# ADC.net
KiCad netlist of a schematic drawn in Altium Designer
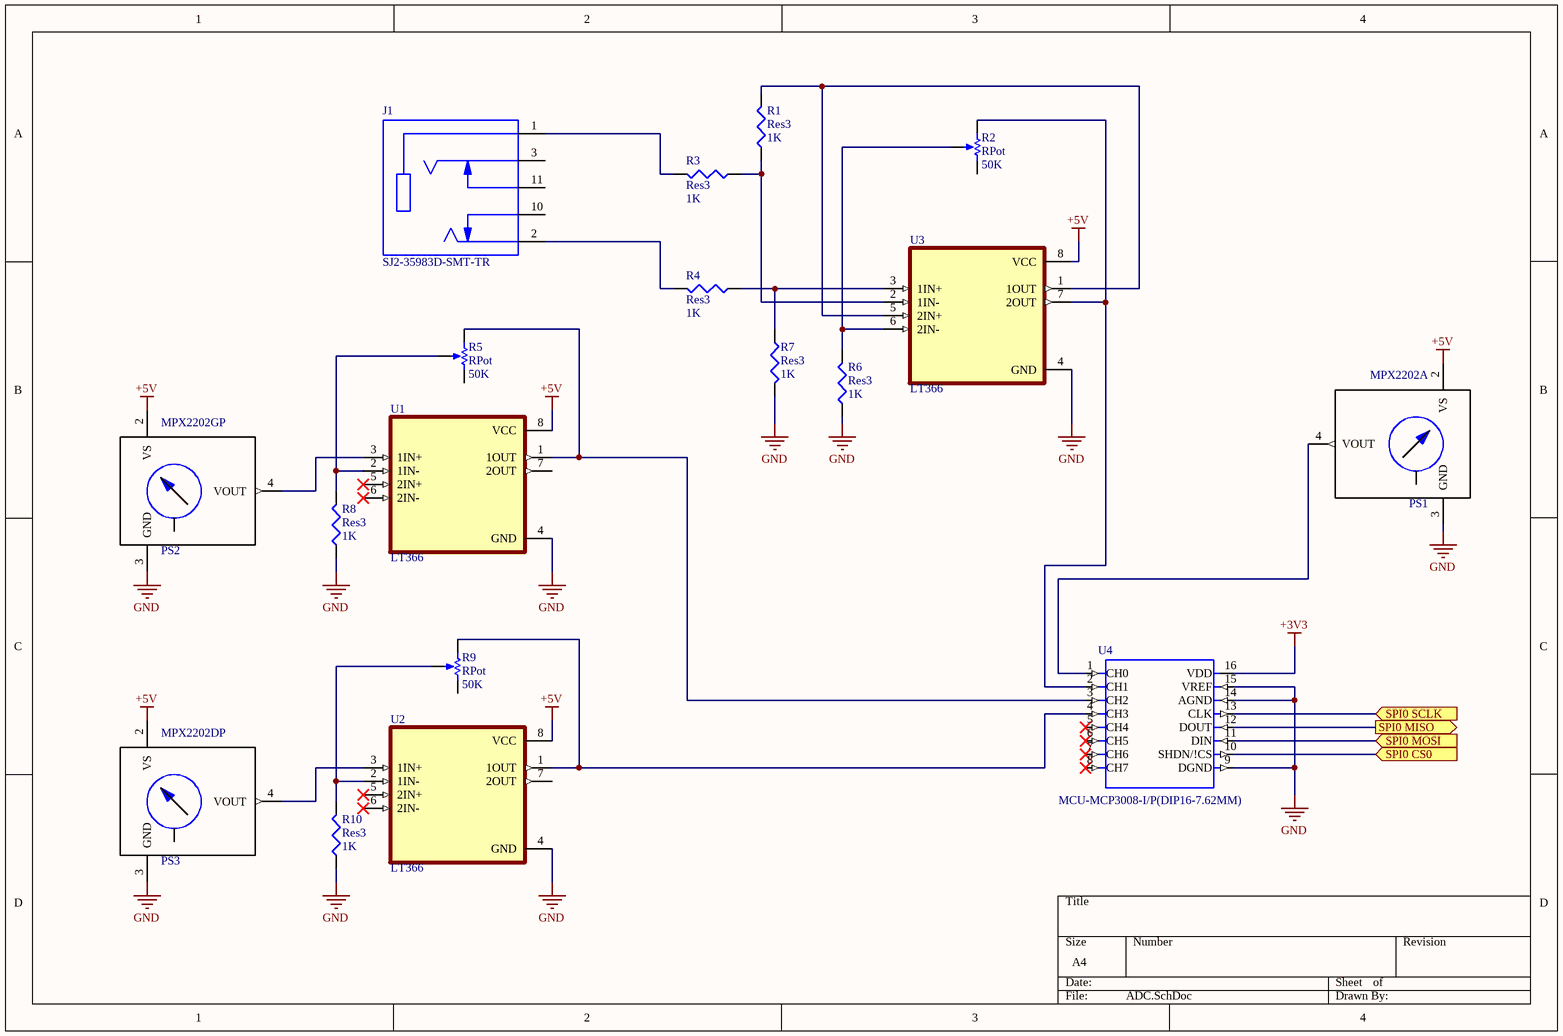
[diagram p0: ADC.SchDoc]

(export (version "E")
  (design (tool "Eeschema 10.0.6"))
  (components
    (comp (ref "J1")
      (value "SJ2-35983D-SMT-TR")
      (footprint "CUI_SJ2-35983D-SMT-TR")
      (description "3 conductor, 3.5 mm, SMT Audio Jack w/ 2 switch")
      (libsource (lib "SJ2-35983D-SMT-TR") (part "SJ2-35983D-SMT-TR"))
    )
    (comp (ref "PS1")
      (value "MPX2202A")
      (footprint "*867-V")
      (description "Low-Side Gate Driver IC Inverting, Non-Inverting 6-MLP (2x2)")
      (fields (field (name "MP") "MPX") (field (name "MF") "ON Semiconductor"))
      (libsource (lib "MPX_____") (part "MPX*****"))
    )
    (comp (ref "PS2")
      (value "MPX2202GP")
      (footprint "*867B-V")
      (description "Low-Side Gate Driver IC Inverting, Non-Inverting 6-MLP (2x2)")
      (fields (field (name "MP") "MPX") (field (name "MF") "ON Semiconductor"))
      (libsource (lib "MPX_____") (part "MPX*****"))
    )
    (comp (ref "PS3")
      (value "MPX2202DP")
      (footprint "*867C-V")
      (description "Low-Side Gate Driver IC Inverting, Non-Inverting 6-MLP (2x2)")
      (fields (field (name "MP") "MPX") (field (name "MF") "ON Semiconductor"))
      (libsource (lib "MPX_____") (part "MPX*****"))
    )
    (comp (ref "R1")
      (value "Res3")
      (footprint "J1-0603")
      (description "Resistor")
      (fields (field (name "ALTIUM_VALUE") "1K") (field (name "PUBLISHER") "Altium Limited"))
      (libsource (lib "Miscellaneous Devices") (part "Res3"))
    )
    (comp (ref "R2")
      (value "RPot")
      (footprint "VR5")
      (description "Potentiometer")
      (fields (field (name "ALTIUM_VALUE") "50K") (field (name "PUBLISHER") "Altium Limited"))
      (libsource (lib "Miscellaneous Devices") (part "RPot"))
    )
    (comp (ref "R3")
      (value "Res3")
      (footprint "J1-0603")
      (description "Resistor")
      (fields (field (name "ALTIUM_VALUE") "1K") (field (name "PUBLISHER") "Altium Limited"))
      (libsource (lib "Miscellaneous Devices") (part "Res3"))
    )
    (comp (ref "R4")
      (value "Res3")
      (footprint "J1-0603")
      (description "Resistor")
      (fields (field (name "ALTIUM_VALUE") "1K") (field (name "PUBLISHER") "Altium Limited"))
      (libsource (lib "Miscellaneous Devices") (part "Res3"))
    )
    (comp (ref "R5")
      (value "RPot")
      (footprint "VR5")
      (description "Potentiometer")
      (fields (field (name "ALTIUM_VALUE") "50K") (field (name "PUBLISHER") "Altium Limited"))
      (libsource (lib "Miscellaneous Devices") (part "RPot"))
    )
    (comp (ref "R6")
      (value "Res3")
      (footprint "J1-0603")
      (description "Resistor")
      (fields (field (name "ALTIUM_VALUE") "1K") (field (name "PUBLISHER") "Altium Limited"))
      (libsource (lib "Miscellaneous Devices") (part "Res3"))
    )
    (comp (ref "R7")
      (value "Res3")
      (footprint "J1-0603")
      (description "Resistor")
      (fields (field (name "ALTIUM_VALUE") "1K") (field (name "PUBLISHER") "Altium Limited"))
      (libsource (lib "Miscellaneous Devices") (part "Res3"))
    )
    (comp (ref "R8")
      (value "Res3")
      (footprint "J1-0603")
      (description "Resistor")
      (fields (field (name "ALTIUM_VALUE") "1K") (field (name "PUBLISHER") "Altium Limited"))
      (libsource (lib "Miscellaneous Devices") (part "Res3"))
    )
    (comp (ref "R9")
      (value "RPot")
      (footprint "VR5")
      (description "Potentiometer")
      (fields (field (name "ALTIUM_VALUE") "50K") (field (name "PUBLISHER") "Altium Limited"))
      (libsource (lib "Miscellaneous Devices") (part "RPot"))
    )
    (comp (ref "R10")
      (value "Res3")
      (footprint "J1-0603")
      (description "Resistor")
      (fields (field (name "ALTIUM_VALUE") "1K") (field (name "PUBLISHER") "Altium Limited"))
      (libsource (lib "Miscellaneous Devices") (part "Res3"))
    )
    (comp (ref "U1")
      (value "LT366")
      (footprint "DIP-8")
      (description "Dual Operational Amplifiers")
      (fields (field (name "MP") "LM358P") (field (name "MF") "Texas Instruments"))
      (libsource (lib "LM358P") (part "LM358P"))
    )
    (comp (ref "U2")
      (value "LT366")
      (footprint "DIP-8")
      (description "Dual Operational Amplifiers")
      (fields (field (name "MP") "LM358P") (field (name "MF") "Texas Instruments"))
      (libsource (lib "LM358P") (part "LM358P"))
    )
    (comp (ref "U3")
      (value "LT366")
      (footprint "DIP-8")
      (description "Dual Operational Amplifiers")
      (fields (field (name "MP") "LM358P") (field (name "MF") "Texas Instruments"))
      (libsource (lib "LM358P") (part "LM358P"))
    )
    (comp (ref "U4")
      (value "MCU-MCP3008-I/P(DIP16-7.62MM)")
      (footprint "DIP16-2.54-19.2X7.62MM")
      (description "10 Bit Analog to Digital Converter 4, 8 Input 1 SAR 16-PDIP")
      (fields (field (name "MF") "Microchip") (field (name "MP") "MCP3008-I/P"))
      (libsource (lib "MCU-MCP3008-I_P_DIP16-7.62MM_") (part "MCU-MCP3008-I/P(DIP16-7.62MM)"))
    )
  )
  (nets
    (net (code "1") (name "+3V3") (class "Default")
      (node (ref "U4") (pin "16") (pinfunction "VDD_16") (pintype "power_in"))
    )
    (net (code "2") (name "+5V") (class "Default")
      (node (ref "PS1") (pin "2") (pinfunction "VS_2") (pintype "power_in"))
      (node (ref "PS2") (pin "2") (pinfunction "VS_2") (pintype "power_in"))
      (node (ref "PS3") (pin "2") (pinfunction "VS_2") (pintype "power_in"))
      (node (ref "U1") (pin "8") (pinfunction "VCC_8") (pintype "power_in"))
      (node (ref "U2") (pin "8") (pinfunction "VCC_8") (pintype "power_in"))
      (node (ref "U3") (pin "8") (pinfunction "VCC_8") (pintype "power_in"))
    )
    (net (code "3") (name "/SPI0 CS0") (class "Default")
      (node (ref "U4") (pin "10") (pinfunction "SHDN/!CS_10") (pintype "output"))
    )
    (net (code "4") (name "/SPI0 MISO") (class "Default")
      (node (ref "U4") (pin "12") (pinfunction "DOUT_12") (pintype "input"))
    )
    (net (code "5") (name "/SPI0 MOSI") (class "Default")
      (node (ref "U4") (pin "11") (pinfunction "DIN_11") (pintype "input"))
    )
    (net (code "6") (name "/SPI0 SCLK") (class "Default")
      (node (ref "U4") (pin "13") (pinfunction "CLK_13") (pintype "output"))
    )
    (net (code "7") (name "GND") (class "Default")
      (node (ref "PS1") (pin "3") (pinfunction "GND_3") (pintype "power_in"))
      (node (ref "PS2") (pin "3") (pinfunction "GND_3") (pintype "power_in"))
      (node (ref "PS3") (pin "3") (pinfunction "GND_3") (pintype "power_in"))
      (node (ref "R10") (pin "1") (pinfunction "1_1") (pintype "passive"))
      (node (ref "R6") (pin "1") (pinfunction "1_1") (pintype "passive"))
      (node (ref "R7") (pin "2") (pinfunction "2_2") (pintype "passive"))
      (node (ref "R8") (pin "1") (pinfunction "1_1") (pintype "passive"))
      (node (ref "U1") (pin "4") (pinfunction "GND_4") (pintype "power_in"))
      (node (ref "U2") (pin "4") (pinfunction "GND_4") (pintype "power_in"))
      (node (ref "U3") (pin "4") (pinfunction "GND_4") (pintype "power_in"))
      (node (ref "U4") (pin "14") (pinfunction "AGND_14") (pintype "input"))
      (node (ref "U4") (pin "15") (pinfunction "VREF_15") (pintype "input"))
      (node (ref "U4") (pin "9") (pinfunction "DGND_9") (pintype "output"))
    )
    (net (code "8") (name "Net-(J1-SLEEVE)") (class "Default")
      (node (ref "J1") (pin "1") (pinfunction "SLEEVE_1") (pintype "passive"))
      (node (ref "R3") (pin "2") (pinfunction "2_2") (pintype "passive"))
    )
    (net (code "9") (name "Net-(J1-TIP)") (class "Default")
      (node (ref "J1") (pin "2") (pinfunction "TIP_2") (pintype "passive"))
      (node (ref "R4") (pin "2") (pinfunction "2_2") (pintype "passive"))
    )
    (net (code "10") (name "Net-(PS1-VOUT)") (class "Default")
      (node (ref "PS1") (pin "4") (pinfunction "VOUT_4") (pintype "output"))
      (node (ref "U4") (pin "1") (pinfunction "CH0_1") (pintype "input"))
    )
    (net (code "11") (name "Net-(PS2-VOUT)") (class "Default")
      (node (ref "PS2") (pin "4") (pinfunction "VOUT_4") (pintype "output"))
      (node (ref "U1") (pin "3") (pinfunction "1IN+_3") (pintype "input"))
    )
    (net (code "12") (name "Net-(PS3-VOUT)") (class "Default")
      (node (ref "PS3") (pin "4") (pinfunction "VOUT_4") (pintype "output"))
      (node (ref "U2") (pin "3") (pinfunction "1IN+_3") (pintype "input"))
    )
    (net (code "13") (name "Net-(R2-TAP)") (class "Default")
      (node (ref "R2") (pin "3") (pinfunction "TAP_3") (pintype "passive"))
      (node (ref "R6") (pin "2") (pinfunction "2_2") (pintype "passive"))
      (node (ref "U3") (pin "6") (pinfunction "2IN-_6") (pintype "input"))
    )
    (net (code "14") (name "Net-(R2-TOP)") (class "Default")
      (node (ref "R2") (pin "1") (pinfunction "TOP_1") (pintype "passive"))
      (node (ref "U3") (pin "7") (pinfunction "2OUT_7") (pintype "output"))
      (node (ref "U4") (pin "2") (pinfunction "CH1_2") (pintype "input"))
    )
    (net (code "15") (name "Net-(R5-TAP)") (class "Default")
      (node (ref "R5") (pin "3") (pinfunction "TAP_3") (pintype "passive"))
      (node (ref "R8") (pin "2") (pinfunction "2_2") (pintype "passive"))
      (node (ref "U1") (pin "2") (pinfunction "1IN-_2") (pintype "input"))
    )
    (net (code "16") (name "Net-(R5-TOP)") (class "Default")
      (node (ref "R5") (pin "1") (pinfunction "TOP_1") (pintype "passive"))
      (node (ref "U1") (pin "1") (pinfunction "1OUT_1") (pintype "output"))
      (node (ref "U4") (pin "3") (pinfunction "CH2_3") (pintype "input"))
    )
    (net (code "17") (name "Net-(R9-TAP)") (class "Default")
      (node (ref "R10") (pin "2") (pinfunction "2_2") (pintype "passive"))
      (node (ref "R9") (pin "3") (pinfunction "TAP_3") (pintype "passive"))
      (node (ref "U2") (pin "2") (pinfunction "1IN-_2") (pintype "input"))
    )
    (net (code "18") (name "Net-(R9-TOP)") (class "Default")
      (node (ref "R9") (pin "1") (pinfunction "TOP_1") (pintype "passive"))
      (node (ref "U2") (pin "1") (pinfunction "1OUT_1") (pintype "output"))
      (node (ref "U4") (pin "4") (pinfunction "CH3_4") (pintype "input"))
    )
    (net (code "19") (name "Net-(U3-1IN+)") (class "Default")
      (node (ref "R4") (pin "1") (pinfunction "1_1") (pintype "passive"))
      (node (ref "R7") (pin "1") (pinfunction "1_1") (pintype "passive"))
      (node (ref "U3") (pin "3") (pinfunction "1IN+_3") (pintype "input"))
    )
    (net (code "20") (name "Net-(U3-1IN-)") (class "Default")
      (node (ref "R1") (pin "1") (pinfunction "1_1") (pintype "passive"))
      (node (ref "R3") (pin "1") (pinfunction "1_1") (pintype "passive"))
      (node (ref "U3") (pin "2") (pinfunction "1IN-_2") (pintype "input"))
    )
    (net (code "21") (name "Net-(U3-1OUT)") (class "Default")
      (node (ref "R1") (pin "2") (pinfunction "2_2") (pintype "passive"))
      (node (ref "U3") (pin "1") (pinfunction "1OUT_1") (pintype "output"))
      (node (ref "U3") (pin "5") (pinfunction "2IN+_5") (pintype "input"))
    )
    (net (code "22") (name "unconnected-(J1-RING1-Pad3)") (class "Default")
      (node (ref "J1") (pin "3") (pinfunction "RING1_3") (pintype "passive"))
    )
    (net (code "23") (name "unconnected-(J1-RING1_SWITCH-Pad11)") (class "Default")
      (node (ref "J1") (pin "11") (pinfunction "RING1_SWITCH_11") (pintype "passive"))
    )
    (net (code "24") (name "unconnected-(J1-TIP_SWITCH-Pad10)") (class "Default")
      (node (ref "J1") (pin "10") (pinfunction "TIP_SWITCH_10") (pintype "passive"))
    )
    (net (code "25") (name "unconnected-(PS1-NC@1-Pad1)") (class "Default")
      (node (ref "PS1") (pin "1") (pinfunction "NC@1_1") (pintype "passive"))
    )
    (net (code "26") (name "unconnected-(PS1-NC@5-Pad5)") (class "Default")
      (node (ref "PS1") (pin "5") (pinfunction "NC@5_5") (pintype "passive"))
    )
    (net (code "27") (name "unconnected-(PS1-NC@6-Pad6)") (class "Default")
      (node (ref "PS1") (pin "6") (pinfunction "NC@6_6") (pintype "passive"))
    )
    (net (code "28") (name "unconnected-(PS2-NC@1-Pad1)") (class "Default")
      (node (ref "PS2") (pin "1") (pinfunction "NC@1_1") (pintype "passive"))
    )
    (net (code "29") (name "unconnected-(PS2-NC@5-Pad5)") (class "Default")
      (node (ref "PS2") (pin "5") (pinfunction "NC@5_5") (pintype "passive"))
    )
    (net (code "30") (name "unconnected-(PS2-NC@6-Pad6)") (class "Default")
      (node (ref "PS2") (pin "6") (pinfunction "NC@6_6") (pintype "passive"))
    )
    (net (code "31") (name "unconnected-(PS3-NC@1-Pad1)") (class "Default")
      (node (ref "PS3") (pin "1") (pinfunction "NC@1_1") (pintype "passive"))
    )
    (net (code "32") (name "unconnected-(PS3-NC@5-Pad5)") (class "Default")
      (node (ref "PS3") (pin "5") (pinfunction "NC@5_5") (pintype "passive"))
    )
    (net (code "33") (name "unconnected-(PS3-NC@6-Pad6)") (class "Default")
      (node (ref "PS3") (pin "6") (pinfunction "NC@6_6") (pintype "passive"))
    )
    (net (code "34") (name "unconnected-(R2-BOT-Pad2)") (class "Default")
      (node (ref "R2") (pin "2") (pinfunction "BOT_2") (pintype "passive"))
    )
    (net (code "35") (name "unconnected-(R5-BOT-Pad2)") (class "Default")
      (node (ref "R5") (pin "2") (pinfunction "BOT_2") (pintype "passive"))
    )
    (net (code "36") (name "unconnected-(R9-BOT-Pad2)") (class "Default")
      (node (ref "R9") (pin "2") (pinfunction "BOT_2") (pintype "passive"))
    )
    (net (code "37") (name "unconnected-(U1-2IN+-Pad5)") (class "Default")
      (node (ref "U1") (pin "5") (pinfunction "2IN+_5") (pintype "input+no_connect"))
    )
    (net (code "38") (name "unconnected-(U1-2IN--Pad6)") (class "Default")
      (node (ref "U1") (pin "6") (pinfunction "2IN-_6") (pintype "input+no_connect"))
    )
    (net (code "39") (name "unconnected-(U1-2OUT-Pad7)") (class "Default")
      (node (ref "U1") (pin "7") (pinfunction "2OUT_7") (pintype "output"))
    )
    (net (code "40") (name "unconnected-(U2-2IN+-Pad5)") (class "Default")
      (node (ref "U2") (pin "5") (pinfunction "2IN+_5") (pintype "input+no_connect"))
    )
    (net (code "41") (name "unconnected-(U2-2IN--Pad6)") (class "Default")
      (node (ref "U2") (pin "6") (pinfunction "2IN-_6") (pintype "input+no_connect"))
    )
    (net (code "42") (name "unconnected-(U2-2OUT-Pad7)") (class "Default")
      (node (ref "U2") (pin "7") (pinfunction "2OUT_7") (pintype "output"))
    )
    (net (code "43") (name "unconnected-(U4-CH4-Pad5)") (class "Default")
      (node (ref "U4") (pin "5") (pinfunction "CH4_5") (pintype "input+no_connect"))
    )
    (net (code "44") (name "unconnected-(U4-CH5-Pad6)") (class "Default")
      (node (ref "U4") (pin "6") (pinfunction "CH5_6") (pintype "input+no_connect"))
    )
    (net (code "45") (name "unconnected-(U4-CH6-Pad7)") (class "Default")
      (node (ref "U4") (pin "7") (pinfunction "CH6_7") (pintype "input+no_connect"))
    )
    (net (code "46") (name "unconnected-(U4-CH7-Pad8)") (class "Default")
      (node (ref "U4") (pin "8") (pinfunction "CH7_8") (pintype "input+no_connect"))
    )
  )
)
